# Sheet1.net
KiCad netlist of a schematic drawn in Altium Designer
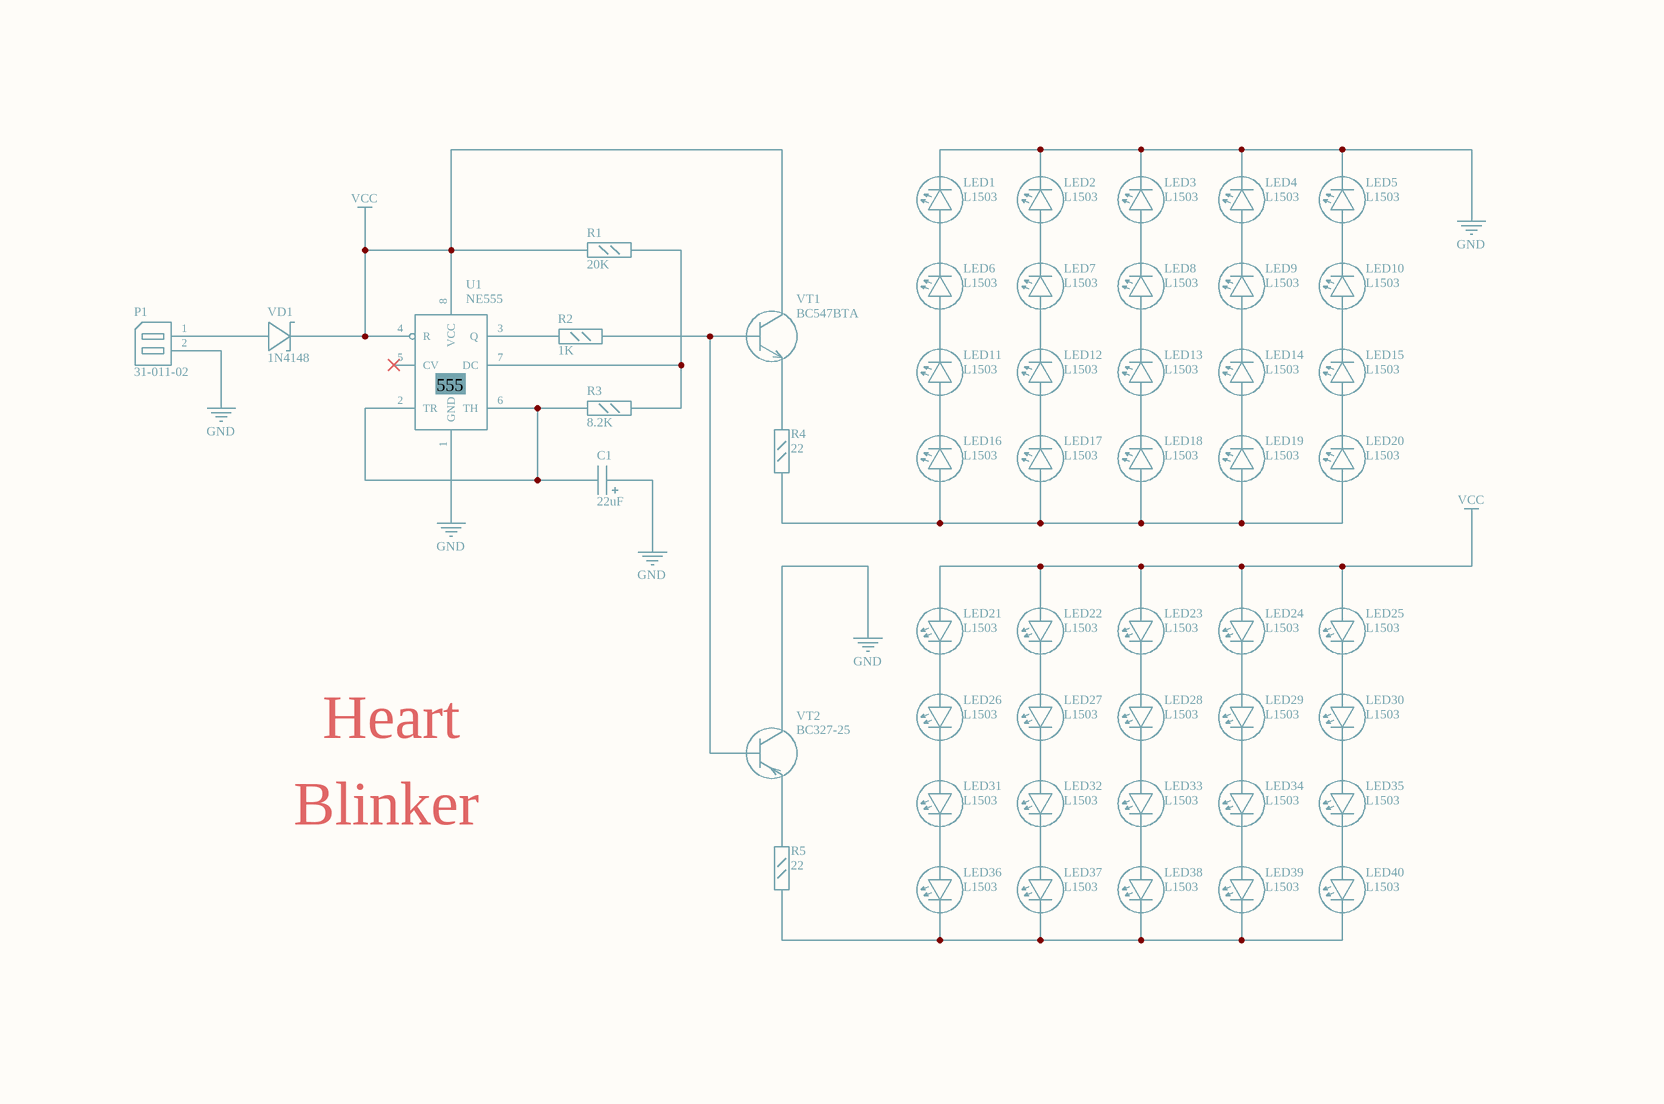
[diagram p0: Sheet1.SchDoc]

(export (version "E")
  (design (tool "Eeschema 10.0.6"))
  (components
    (comp (ref "C1") (value "22uF") (footprint "CAP_POL5") (libsource (lib "CustomMillLib") (part "Cap_Pol")))
    (comp (ref "LED1")
      (value "L1503")
      (footprint "LED2.54-5MM-GREEN")
      (libsource (lib "Hi-Tech FireAlarm") (part "Led"))
    )
    (comp (ref "LED2")
      (value "L1503")
      (footprint "LED2.54-5MM-GREEN")
      (libsource (lib "Hi-Tech FireAlarm") (part "Led"))
    )
    (comp (ref "LED3")
      (value "L1503")
      (footprint "LED2.54-5MM-GREEN")
      (libsource (lib "Hi-Tech FireAlarm") (part "Led"))
    )
    (comp (ref "LED4")
      (value "L1503")
      (footprint "LED2.54-5MM-GREEN")
      (libsource (lib "Hi-Tech FireAlarm") (part "Led"))
    )
    (comp (ref "LED5")
      (value "L1503")
      (footprint "LED2.54-5MM-GREEN")
      (libsource (lib "Hi-Tech FireAlarm") (part "Led"))
    )
    (comp (ref "LED6")
      (value "L1503")
      (footprint "LED2.54-5MM-GREEN")
      (libsource (lib "Hi-Tech FireAlarm") (part "Led"))
    )
    (comp (ref "LED7")
      (value "L1503")
      (footprint "LED2.54-5MM-GREEN")
      (libsource (lib "Hi-Tech FireAlarm") (part "Led"))
    )
    (comp (ref "LED8")
      (value "L1503")
      (footprint "LED2.54-5MM-GREEN")
      (libsource (lib "Hi-Tech FireAlarm") (part "Led"))
    )
    (comp (ref "LED9")
      (value "L1503")
      (footprint "LED2.54-5MM-GREEN")
      (libsource (lib "Hi-Tech FireAlarm") (part "Led"))
    )
    (comp (ref "LED10")
      (value "L1503")
      (footprint "LED2.54-5MM-GREEN")
      (libsource (lib "Hi-Tech FireAlarm") (part "Led"))
    )
    (comp (ref "LED11")
      (value "L1503")
      (footprint "LED2.54-5MM-GREEN")
      (libsource (lib "Hi-Tech FireAlarm") (part "Led"))
    )
    (comp (ref "LED12")
      (value "L1503")
      (footprint "LED2.54-5MM-GREEN")
      (libsource (lib "Hi-Tech FireAlarm") (part "Led"))
    )
    (comp (ref "LED13")
      (value "L1503")
      (footprint "LED2.54-5MM-GREEN")
      (libsource (lib "Hi-Tech FireAlarm") (part "Led"))
    )
    (comp (ref "LED14")
      (value "L1503")
      (footprint "LED2.54-5MM-GREEN")
      (libsource (lib "Hi-Tech FireAlarm") (part "Led"))
    )
    (comp (ref "LED15")
      (value "L1503")
      (footprint "LED2.54-5MM-GREEN")
      (libsource (lib "Hi-Tech FireAlarm") (part "Led"))
    )
    (comp (ref "LED16")
      (value "L1503")
      (footprint "LED2.54-5MM-GREEN")
      (libsource (lib "Hi-Tech FireAlarm") (part "Led"))
    )
    (comp (ref "LED17")
      (value "L1503")
      (footprint "LED2.54-5MM-GREEN")
      (libsource (lib "Hi-Tech FireAlarm") (part "Led"))
    )
    (comp (ref "LED18")
      (value "L1503")
      (footprint "LED2.54-5MM-GREEN")
      (libsource (lib "Hi-Tech FireAlarm") (part "Led"))
    )
    (comp (ref "LED19")
      (value "L1503")
      (footprint "LED2.54-5MM-GREEN")
      (libsource (lib "Hi-Tech FireAlarm") (part "Led"))
    )
    (comp (ref "LED20")
      (value "L1503")
      (footprint "LED2.54-5MM-GREEN")
      (libsource (lib "Hi-Tech FireAlarm") (part "Led"))
    )
    (comp (ref "LED21")
      (value "L1503")
      (footprint "LED2.54-5MM-GREEN")
      (libsource (lib "Hi-Tech FireAlarm") (part "Led"))
    )
    (comp (ref "LED22")
      (value "L1503")
      (footprint "LED2.54-5MM-GREEN")
      (libsource (lib "Hi-Tech FireAlarm") (part "Led"))
    )
    (comp (ref "LED23")
      (value "L1503")
      (footprint "LED2.54-5MM-GREEN")
      (libsource (lib "Hi-Tech FireAlarm") (part "Led"))
    )
    (comp (ref "LED24")
      (value "L1503")
      (footprint "LED2.54-5MM-GREEN")
      (libsource (lib "Hi-Tech FireAlarm") (part "Led"))
    )
    (comp (ref "LED25")
      (value "L1503")
      (footprint "LED2.54-5MM-GREEN")
      (libsource (lib "Hi-Tech FireAlarm") (part "Led"))
    )
    (comp (ref "LED26")
      (value "L1503")
      (footprint "LED2.54-5MM-GREEN")
      (libsource (lib "Hi-Tech FireAlarm") (part "Led"))
    )
    (comp (ref "LED27")
      (value "L1503")
      (footprint "LED2.54-5MM-GREEN")
      (libsource (lib "Hi-Tech FireAlarm") (part "Led"))
    )
    (comp (ref "LED28")
      (value "L1503")
      (footprint "LED2.54-5MM-GREEN")
      (libsource (lib "Hi-Tech FireAlarm") (part "Led"))
    )
    (comp (ref "LED29")
      (value "L1503")
      (footprint "LED2.54-5MM-GREEN")
      (libsource (lib "Hi-Tech FireAlarm") (part "Led"))
    )
    (comp (ref "LED30")
      (value "L1503")
      (footprint "LED2.54-5MM-GREEN")
      (libsource (lib "Hi-Tech FireAlarm") (part "Led"))
    )
    (comp (ref "LED31")
      (value "L1503")
      (footprint "LED2.54-5MM-GREEN")
      (libsource (lib "Hi-Tech FireAlarm") (part "Led"))
    )
    (comp (ref "LED32")
      (value "L1503")
      (footprint "LED2.54-5MM-GREEN")
      (libsource (lib "Hi-Tech FireAlarm") (part "Led"))
    )
    (comp (ref "LED33")
      (value "L1503")
      (footprint "LED2.54-5MM-GREEN")
      (libsource (lib "Hi-Tech FireAlarm") (part "Led"))
    )
    (comp (ref "LED34")
      (value "L1503")
      (footprint "LED2.54-5MM-GREEN")
      (libsource (lib "Hi-Tech FireAlarm") (part "Led"))
    )
    (comp (ref "LED35")
      (value "L1503")
      (footprint "LED2.54-5MM-GREEN")
      (libsource (lib "Hi-Tech FireAlarm") (part "Led"))
    )
    (comp (ref "LED36")
      (value "L1503")
      (footprint "LED2.54-5MM-GREEN")
      (libsource (lib "Hi-Tech FireAlarm") (part "Led"))
    )
    (comp (ref "LED37")
      (value "L1503")
      (footprint "LED2.54-5MM-GREEN")
      (libsource (lib "Hi-Tech FireAlarm") (part "Led"))
    )
    (comp (ref "LED38")
      (value "L1503")
      (footprint "LED2.54-5MM-GREEN")
      (libsource (lib "Hi-Tech FireAlarm") (part "Led"))
    )
    (comp (ref "LED39")
      (value "L1503")
      (footprint "LED2.54-5MM-GREEN")
      (libsource (lib "Hi-Tech FireAlarm") (part "Led"))
    )
    (comp (ref "LED40")
      (value "L1503")
      (footprint "LED2.54-5MM-GREEN")
      (libsource (lib "Hi-Tech FireAlarm") (part "Led"))
    )
    (comp (ref "P1") (value "31-011-02") (footprint "H2-5.08") (libsource (lib "Connectors") (part "CHOP2")))
    (comp (ref "R1") (value "20K") (footprint "AXIAL10R") (libsource (lib "CustomMillLib") (part "Res")))
    (comp (ref "R2") (value "1K") (footprint "R0805") (libsource (lib "Hi-Tech FireAlarm") (part "Res")))
    (comp (ref "R3") (value "8.2K") (footprint "AXIAL10R") (libsource (lib "CustomMillLib") (part "Res")))
    (comp (ref "R4") (value "22") (footprint "AXIAL10R") (libsource (lib "CustomMillLib") (part "Res")))
    (comp (ref "R5") (value "22") (footprint "R0805") (libsource (lib "Hi-Tech FireAlarm") (part "Res")))
    (comp (ref "U1") (value "NE555") (footprint "SOIC8") (libsource (lib "Hi-Tech FireAlarm") (part "NE555")))
    (comp (ref "VD1")
      (value "1N4148")
      (footprint "AXIAL10D-BL")
      (libsource (lib "CustomMillLib") (part "Diode_Sc"))
    )
    (comp (ref "VT1")
      (value "BC547BTA")
      (footprint "TO-92")
      (libsource (lib "CustomMillLib") (part "Transistor_NPN"))
    )
    (comp (ref "VT2")
      (value "BC327-25")
      (footprint "TO-92")
      (libsource (lib "CustomMillLib") (part "Transistor_PNP"))
    )
  )
  (nets
    (net (code "1") (name "GND") (class "Default")
      (node (ref "C1") (pin "1") (pinfunction "61_1") (pintype "passive"))
      (node (ref "LED1") (pin "2") (pinfunction "6_2") (pintype "passive"))
      (node (ref "LED2") (pin "2") (pinfunction "6_2") (pintype "passive"))
      (node (ref "LED3") (pin "2") (pinfunction "6_2") (pintype "passive"))
      (node (ref "LED4") (pin "2") (pinfunction "6_2") (pintype "passive"))
      (node (ref "LED5") (pin "2") (pinfunction "6_2") (pintype "passive"))
      (node (ref "P1") (pin "2") (pinfunction "2_2") (pintype "passive"))
      (node (ref "U1") (pin "1") (pinfunction "GND_1") (pintype "passive"))
      (node (ref "VT2") (pin "1") (pinfunction "9_1") (pintype "passive"))
    )
    (net (code "2") (name "Net-(C1-62)") (class "Default")
      (node (ref "C1") (pin "2") (pinfunction "62_2") (pintype "passive"))
      (node (ref "R3") (pin "2") (pinfunction "2_2") (pintype "passive"))
      (node (ref "U1") (pin "2") (pinfunction "TR_2") (pintype "passive"))
      (node (ref "U1") (pin "6") (pinfunction "TH_6") (pintype "passive"))
    )
    (net (code "3") (name "Net-(LED1-5)") (class "Default")
      (node (ref "LED1") (pin "1") (pinfunction "5_1") (pintype "passive"))
      (node (ref "LED6") (pin "2") (pinfunction "6_2") (pintype "passive"))
    )
    (net (code "4") (name "Net-(LED2-5)") (class "Default")
      (node (ref "LED2") (pin "1") (pinfunction "5_1") (pintype "passive"))
      (node (ref "LED7") (pin "2") (pinfunction "6_2") (pintype "passive"))
    )
    (net (code "5") (name "Net-(LED3-5)") (class "Default")
      (node (ref "LED3") (pin "1") (pinfunction "5_1") (pintype "passive"))
      (node (ref "LED8") (pin "2") (pinfunction "6_2") (pintype "passive"))
    )
    (net (code "6") (name "Net-(LED4-5)") (class "Default")
      (node (ref "LED4") (pin "1") (pinfunction "5_1") (pintype "passive"))
      (node (ref "LED9") (pin "2") (pinfunction "6_2") (pintype "passive"))
    )
    (net (code "7") (name "Net-(LED10-5)") (class "Default")
      (node (ref "LED10") (pin "1") (pinfunction "5_1") (pintype "passive"))
      (node (ref "LED15") (pin "2") (pinfunction "6_2") (pintype "passive"))
    )
    (net (code "8") (name "Net-(LED10-6)") (class "Default")
      (node (ref "LED10") (pin "2") (pinfunction "6_2") (pintype "passive"))
      (node (ref "LED5") (pin "1") (pinfunction "5_1") (pintype "passive"))
    )
    (net (code "9") (name "Net-(LED11-5)") (class "Default")
      (node (ref "LED11") (pin "1") (pinfunction "5_1") (pintype "passive"))
      (node (ref "LED16") (pin "2") (pinfunction "6_2") (pintype "passive"))
    )
    (net (code "10") (name "Net-(LED11-6)") (class "Default")
      (node (ref "LED11") (pin "2") (pinfunction "6_2") (pintype "passive"))
      (node (ref "LED6") (pin "1") (pinfunction "5_1") (pintype "passive"))
    )
    (net (code "11") (name "Net-(LED12-5)") (class "Default")
      (node (ref "LED12") (pin "1") (pinfunction "5_1") (pintype "passive"))
      (node (ref "LED17") (pin "2") (pinfunction "6_2") (pintype "passive"))
    )
    (net (code "12") (name "Net-(LED12-6)") (class "Default")
      (node (ref "LED12") (pin "2") (pinfunction "6_2") (pintype "passive"))
      (node (ref "LED7") (pin "1") (pinfunction "5_1") (pintype "passive"))
    )
    (net (code "13") (name "Net-(LED13-5)") (class "Default")
      (node (ref "LED13") (pin "1") (pinfunction "5_1") (pintype "passive"))
      (node (ref "LED18") (pin "2") (pinfunction "6_2") (pintype "passive"))
    )
    (net (code "14") (name "Net-(LED13-6)") (class "Default")
      (node (ref "LED13") (pin "2") (pinfunction "6_2") (pintype "passive"))
      (node (ref "LED8") (pin "1") (pinfunction "5_1") (pintype "passive"))
    )
    (net (code "15") (name "Net-(LED14-5)") (class "Default")
      (node (ref "LED14") (pin "1") (pinfunction "5_1") (pintype "passive"))
      (node (ref "LED19") (pin "2") (pinfunction "6_2") (pintype "passive"))
    )
    (net (code "16") (name "Net-(LED14-6)") (class "Default")
      (node (ref "LED14") (pin "2") (pinfunction "6_2") (pintype "passive"))
      (node (ref "LED9") (pin "1") (pinfunction "5_1") (pintype "passive"))
    )
    (net (code "17") (name "Net-(LED15-5)") (class "Default")
      (node (ref "LED15") (pin "1") (pinfunction "5_1") (pintype "passive"))
      (node (ref "LED20") (pin "2") (pinfunction "6_2") (pintype "passive"))
    )
    (net (code "18") (name "Net-(LED16-5)") (class "Default")
      (node (ref "LED16") (pin "1") (pinfunction "5_1") (pintype "passive"))
      (node (ref "LED17") (pin "1") (pinfunction "5_1") (pintype "passive"))
      (node (ref "LED18") (pin "1") (pinfunction "5_1") (pintype "passive"))
      (node (ref "LED19") (pin "1") (pinfunction "5_1") (pintype "passive"))
      (node (ref "LED20") (pin "1") (pinfunction "5_1") (pintype "passive"))
      (node (ref "R4") (pin "1") (pinfunction "2_1") (pintype "passive"))
    )
    (net (code "19") (name "Net-(LED21-6)") (class "Default")
      (node (ref "LED21") (pin "2") (pinfunction "6_2") (pintype "passive"))
      (node (ref "LED26") (pin "1") (pinfunction "5_1") (pintype "passive"))
    )
    (net (code "20") (name "Net-(LED22-6)") (class "Default")
      (node (ref "LED22") (pin "2") (pinfunction "6_2") (pintype "passive"))
      (node (ref "LED27") (pin "1") (pinfunction "5_1") (pintype "passive"))
    )
    (net (code "21") (name "Net-(LED23-6)") (class "Default")
      (node (ref "LED23") (pin "2") (pinfunction "6_2") (pintype "passive"))
      (node (ref "LED28") (pin "1") (pinfunction "5_1") (pintype "passive"))
    )
    (net (code "22") (name "Net-(LED24-6)") (class "Default")
      (node (ref "LED24") (pin "2") (pinfunction "6_2") (pintype "passive"))
      (node (ref "LED29") (pin "1") (pinfunction "5_1") (pintype "passive"))
    )
    (net (code "23") (name "Net-(LED25-6)") (class "Default")
      (node (ref "LED25") (pin "2") (pinfunction "6_2") (pintype "passive"))
      (node (ref "LED30") (pin "1") (pinfunction "5_1") (pintype "passive"))
    )
    (net (code "24") (name "Net-(LED26-6)") (class "Default")
      (node (ref "LED26") (pin "2") (pinfunction "6_2") (pintype "passive"))
      (node (ref "LED31") (pin "1") (pinfunction "5_1") (pintype "passive"))
    )
    (net (code "25") (name "Net-(LED27-6)") (class "Default")
      (node (ref "LED27") (pin "2") (pinfunction "6_2") (pintype "passive"))
      (node (ref "LED32") (pin "1") (pinfunction "5_1") (pintype "passive"))
    )
    (net (code "26") (name "Net-(LED28-6)") (class "Default")
      (node (ref "LED28") (pin "2") (pinfunction "6_2") (pintype "passive"))
      (node (ref "LED33") (pin "1") (pinfunction "5_1") (pintype "passive"))
    )
    (net (code "27") (name "Net-(LED29-6)") (class "Default")
      (node (ref "LED29") (pin "2") (pinfunction "6_2") (pintype "passive"))
      (node (ref "LED34") (pin "1") (pinfunction "5_1") (pintype "passive"))
    )
    (net (code "28") (name "Net-(LED30-6)") (class "Default")
      (node (ref "LED30") (pin "2") (pinfunction "6_2") (pintype "passive"))
      (node (ref "LED35") (pin "1") (pinfunction "5_1") (pintype "passive"))
    )
    (net (code "29") (name "Net-(LED31-6)") (class "Default")
      (node (ref "LED31") (pin "2") (pinfunction "6_2") (pintype "passive"))
      (node (ref "LED36") (pin "1") (pinfunction "5_1") (pintype "passive"))
    )
    (net (code "30") (name "Net-(LED32-6)") (class "Default")
      (node (ref "LED32") (pin "2") (pinfunction "6_2") (pintype "passive"))
      (node (ref "LED37") (pin "1") (pinfunction "5_1") (pintype "passive"))
    )
    (net (code "31") (name "Net-(LED33-6)") (class "Default")
      (node (ref "LED33") (pin "2") (pinfunction "6_2") (pintype "passive"))
      (node (ref "LED38") (pin "1") (pinfunction "5_1") (pintype "passive"))
    )
    (net (code "32") (name "Net-(LED34-6)") (class "Default")
      (node (ref "LED34") (pin "2") (pinfunction "6_2") (pintype "passive"))
      (node (ref "LED39") (pin "1") (pinfunction "5_1") (pintype "passive"))
    )
    (net (code "33") (name "Net-(LED35-6)") (class "Default")
      (node (ref "LED35") (pin "2") (pinfunction "6_2") (pintype "passive"))
      (node (ref "LED40") (pin "1") (pinfunction "5_1") (pintype "passive"))
    )
    (net (code "34") (name "Net-(LED36-6)") (class "Default")
      (node (ref "LED36") (pin "2") (pinfunction "6_2") (pintype "passive"))
      (node (ref "LED37") (pin "2") (pinfunction "6_2") (pintype "passive"))
      (node (ref "LED38") (pin "2") (pinfunction "6_2") (pintype "passive"))
      (node (ref "LED39") (pin "2") (pinfunction "6_2") (pintype "passive"))
      (node (ref "LED40") (pin "2") (pinfunction "6_2") (pintype "passive"))
      (node (ref "R5") (pin "1") (pinfunction "2_1") (pintype "passive"))
    )
    (net (code "35") (name "Net-(U1-DC)") (class "Default")
      (node (ref "R1") (pin "1") (pinfunction "2_1") (pintype "passive"))
      (node (ref "R3") (pin "1") (pinfunction "2_1") (pintype "passive"))
      (node (ref "U1") (pin "7") (pinfunction "DC_7") (pintype "passive"))
    )
    (net (code "36") (name "Net-(U1-Q)") (class "Default")
      (node (ref "R2") (pin "1") (pinfunction "2_1") (pintype "passive"))
      (node (ref "U1") (pin "3") (pinfunction "Q_3") (pintype "passive"))
    )
    (net (code "37") (name "Net-(VD1-63)") (class "Default")
      (node (ref "P1") (pin "1") (pinfunction "1_1") (pintype "passive"))
      (node (ref "VD1") (pin "1") (pinfunction "63_1") (pintype "passive"))
    )
    (net (code "38") (name "Net-(VT1-10)") (class "Default")
      (node (ref "R2") (pin "2") (pinfunction "2_2") (pintype "passive"))
      (node (ref "VT1") (pin "2") (pinfunction "10_2") (pintype "passive"))
      (node (ref "VT2") (pin "2") (pinfunction "10_2") (pintype "passive"))
    )
    (net (code "39") (name "Net-(VT1-11)") (class "Default")
      (node (ref "R4") (pin "2") (pinfunction "2_2") (pintype "passive"))
      (node (ref "VT1") (pin "3") (pinfunction "11_3") (pintype "passive"))
    )
    (net (code "40") (name "Net-(VT2-11)") (class "Default")
      (node (ref "R5") (pin "2") (pinfunction "2_2") (pintype "passive"))
      (node (ref "VT2") (pin "3") (pinfunction "11_3") (pintype "passive"))
    )
    (net (code "41") (name "VCC") (class "Default")
      (node (ref "LED21") (pin "1") (pinfunction "5_1") (pintype "passive"))
      (node (ref "LED22") (pin "1") (pinfunction "5_1") (pintype "passive"))
      (node (ref "LED23") (pin "1") (pinfunction "5_1") (pintype "passive"))
      (node (ref "LED24") (pin "1") (pinfunction "5_1") (pintype "passive"))
      (node (ref "LED25") (pin "1") (pinfunction "5_1") (pintype "passive"))
      (node (ref "R1") (pin "2") (pinfunction "2_2") (pintype "passive"))
      (node (ref "U1") (pin "4") (pinfunction "R_4") (pintype "passive"))
      (node (ref "U1") (pin "8") (pinfunction "VCC_8") (pintype "passive"))
      (node (ref "VD1") (pin "2") (pinfunction "64_2") (pintype "passive"))
      (node (ref "VT1") (pin "1") (pinfunction "9_1") (pintype "passive"))
    )
    (net (code "42") (name "unconnected-(U1-CV-Pad5)") (class "Default")
      (node (ref "U1") (pin "5") (pinfunction "CV_5") (pintype "passive+no_connect"))
    )
  )
)
